# CONNECTIONS.net
KiCad netlist of a schematic drawn in Altium Designer
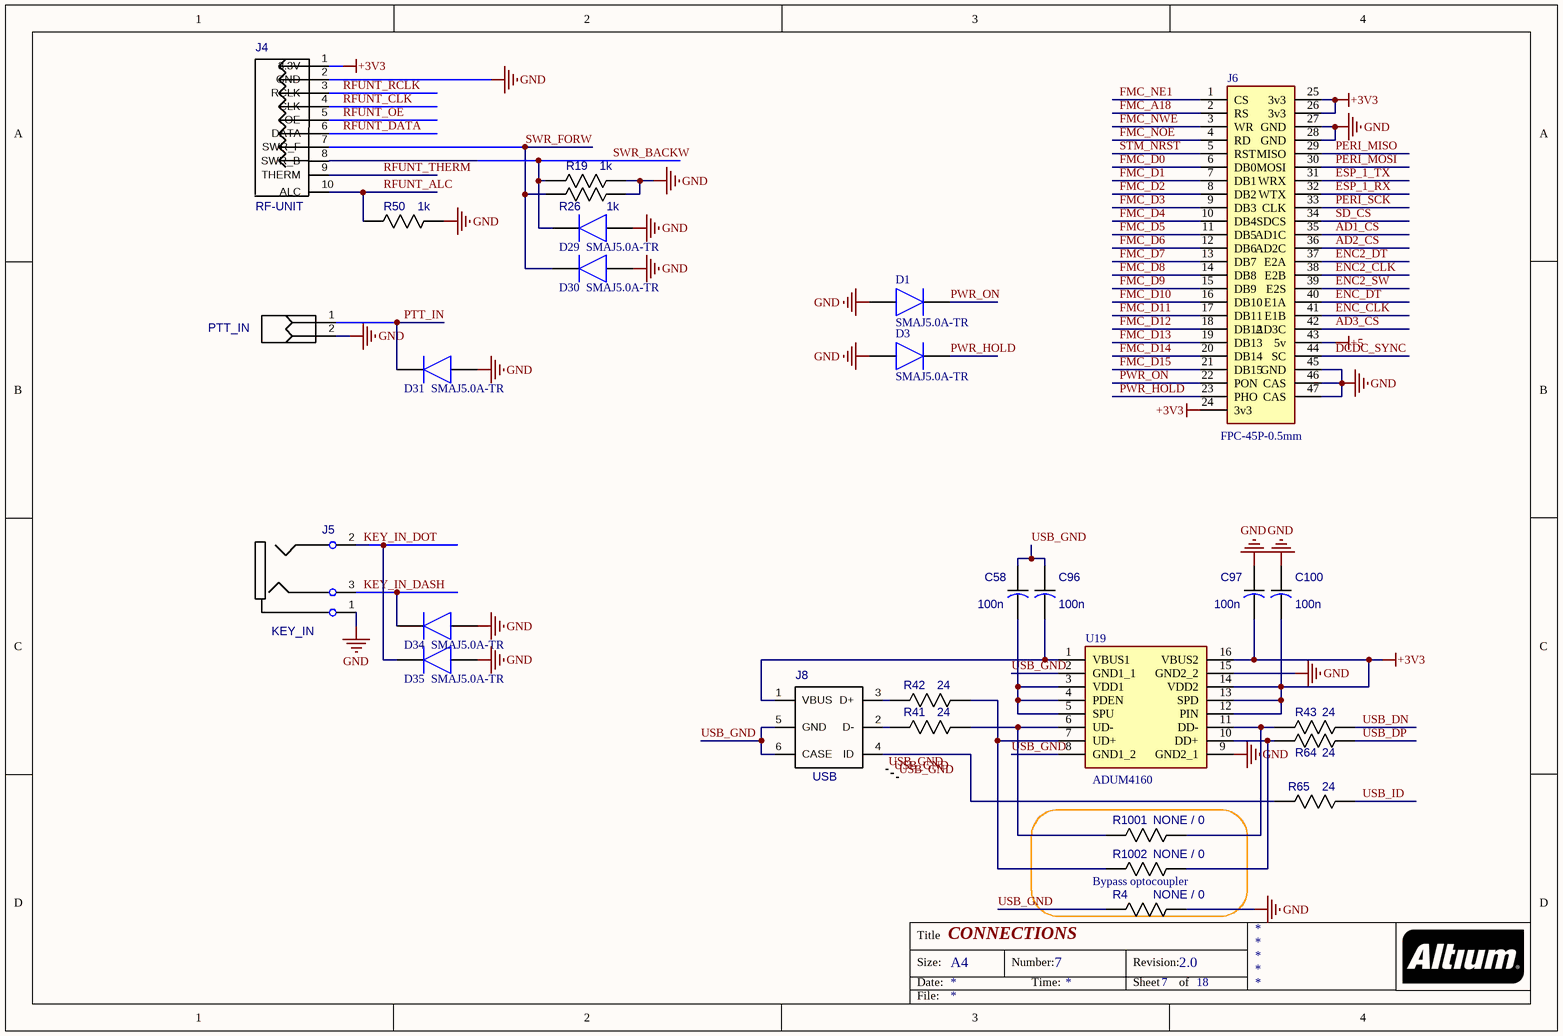
[diagram p0: CONNECTIONS.SchDoc]

(export (version "E")
  (design (tool "Eeschema 10.0.6"))
  (components
    (comp (ref "C58")
      (value "100n")
      (footprint "CAP_0805")
      (description "CAP_0805")
      (libsource (lib "*") (part "CAP_0805"))
    )
    (comp (ref "C96")
      (value "100n")
      (footprint "CAP_0805")
      (description "CAP_0805")
      (libsource (lib "*") (part "CAP_0805"))
    )
    (comp (ref "C97")
      (value "100n")
      (footprint "CAP_0805")
      (description "CAP_0805")
      (libsource (lib "*") (part "CAP_0805"))
    )
    (comp (ref "C100")
      (value "100n")
      (footprint "CAP_0805")
      (description "CAP_0805")
      (libsource (lib "*") (part "CAP_0805"))
    )
    (comp (ref "D1")
      (value "SMAJ5.0A-TR")
      (footprint "SMBJ36CATR")
      (description "Diode")
      (fields
        (field (name "MANUFACTURER_PART_NUMBER") "SMLVT3V3")
        (field (name "MOUSER PART NUMBER") "511-SMLVT3V3")
      )
      (libsource (lib "*") (part "SMLVT3V3"))
    )
    (comp (ref "D3")
      (value "SMAJ5.0A-TR")
      (footprint "SMBJ36CATR")
      (description "Diode")
      (fields
        (field (name "MANUFACTURER_PART_NUMBER") "SMLVT3V3")
        (field (name "MOUSER PART NUMBER") "511-SMLVT3V3")
      )
      (libsource (lib "*") (part "SMLVT3V3"))
    )
    (comp (ref "D29")
      (value "SMAJ5.0A-TR")
      (footprint "SamacSys:SMBJ36CATR")
      (description "Diode")
      (fields
        (field (name "MANUFACTURER_PART_NUMBER") "SMLVT3V3")
        (field (name "MOUSER PART NUMBER") "511-SMLVT3V3")
      )
      (libsource (lib "*") (part "SMLVT3V3"))
    )
    (comp (ref "D30")
      (value "SMAJ5.0A-TR")
      (footprint "SMBJ36CATR")
      (description "Diode")
      (fields
        (field (name "MANUFACTURER_PART_NUMBER") "SMLVT3V3")
        (field (name "MOUSER PART NUMBER") "511-SMLVT3V3")
      )
      (libsource (lib "*") (part "SMLVT3V3"))
    )
    (comp (ref "D31")
      (value "SMAJ5.0A-TR")
      (footprint "SamacSys:SMBJ36CATR")
      (description "Diode")
      (fields
        (field (name "MANUFACTURER_PART_NUMBER") "SMLVT3V3")
        (field (name "MOUSER PART NUMBER") "511-SMLVT3V3")
      )
      (libsource (lib "*") (part "SMLVT3V3"))
    )
    (comp (ref "D34")
      (value "SMAJ5.0A-TR")
      (footprint "SamacSys:SMBJ36CATR")
      (description "Diode")
      (fields
        (field (name "MANUFACTURER_PART_NUMBER") "SMLVT3V3")
        (field (name "MOUSER PART NUMBER") "511-SMLVT3V3")
      )
      (libsource (lib "*") (part "SMLVT3V3"))
    )
    (comp (ref "D35")
      (value "SMAJ5.0A-TR")
      (footprint "SamacSys:SMBJ36CATR")
      (description "Diode")
      (fields
        (field (name "MANUFACTURER_PART_NUMBER") "SMLVT3V3")
        (field (name "MOUSER PART NUMBER") "511-SMLVT3V3")
      )
      (libsource (lib "*") (part "SMLVT3V3"))
    )
    (comp (ref "J4")
      (value "RF-UNIT")
      (footprint "90131-0126")
      (description "2*5 Pin")
      (libsource (lib "MOTHERBOARD") (part "90131-0126"))
    )
    (comp (ref "J5")
      (value "KEY_IN")
      (footprint "SJ1-3525NG")
      (description "SJ1-3525NG")
      (libsource (lib "*") (part "SJ1-3523N"))
    )
    (comp (ref "J6")
      (value "FPC-45P-0.5mm")
      (footprint "MOTHERBOARD:FH12S45S05SH60")
      (description "Connector")
      (fields
        (field (name "MANUFACTURER_PART_NUMBER") "FH12S-45S-0.5SH(55)")
        (field (name "MOUSER PART NUMBER") "798-FH12S-45S-05SH55")
      )
      (libsource (lib "*") (part "FH12S-45S-0.5SH_55_"))
    )
    (comp (ref "J8")
      (value "USB")
      (footprint "2-1734035-3")
      (description "2-1734035-3")
      (libsource (lib "*") (part "2-1734035-3"))
    )
    (comp (ref "PTT_IN")
      (value "PTT_IN")
      (footprint "51022-0200")
      (description "51022-0200")
      (libsource (lib "*") (part "51022-0200"))
    )
    (comp (ref "R4")
      (value "NONE / 0")
      (footprint "RES_0805")
      (description "RES_0805")
      (libsource (lib "*") (part "RES_0805"))
    )
    (comp (ref "R19")
      (value "1k")
      (footprint "RES_0805")
      (description "RES_0805")
      (libsource (lib "*") (part "RES_0805"))
    )
    (comp (ref "R26")
      (value "1k")
      (footprint "RES_0805")
      (description "RES_0805")
      (libsource (lib "*") (part "RES_0805"))
    )
    (comp (ref "R41")
      (value "24")
      (footprint "RES_0805")
      (description "RES_0805")
      (libsource (lib "*") (part "RES_0805"))
    )
    (comp (ref "R42")
      (value "24")
      (footprint "RES_0805")
      (description "RES_0805")
      (libsource (lib "*") (part "RES_0805"))
    )
    (comp (ref "R43")
      (value "24")
      (footprint "RES_0805")
      (description "RES_0805")
      (libsource (lib "*") (part "RES_0805"))
    )
    (comp (ref "R50")
      (value "1k")
      (footprint "RES_0805")
      (description "RES_0805")
      (libsource (lib "*") (part "RES_0805"))
    )
    (comp (ref "R64")
      (value "24")
      (footprint "RES_0805")
      (description "RES_0805")
      (libsource (lib "*") (part "RES_0805"))
    )
    (comp (ref "R65")
      (value "24")
      (footprint "RES_0805")
      (description "RES_0805")
      (libsource (lib "*") (part "RES_0805"))
    )
    (comp (ref "R1001")
      (value "NONE / 0")
      (footprint "RES_0805")
      (description "RES_0805")
      (libsource (lib "*") (part "RES_0805"))
    )
    (comp (ref "R1002")
      (value "NONE / 0")
      (footprint "RES_0805")
      (description "RES_0805")
      (libsource (lib "*") (part "RES_0805"))
    )
    (comp (ref "U19")
      (value "ADUM4160")
      (footprint "SOIC127P1032X265-16N")
      (description "Integrated Circuit")
      (fields
        (field (name "MANUFACTURER_PART_NUMBER") "ADUM4160BRWZ")
        (field (name "MOUSER PART NUMBER") "584-ADUM4160BRWZ")
      )
      (libsource (lib "*") (part "ADUM4160BRWZ"))
    )
  )
  (nets
    (net (code "1") (name "+3V3") (class "Default")
      (node (ref "C100") (pin "2") (pinfunction "2_2") (pintype "passive"))
      (node (ref "C97") (pin "2") (pinfunction "2_2") (pintype "passive"))
      (node (ref "J4") (pin "1") (pinfunction "3.3V_1") (pintype "passive"))
      (node (ref "J6") (pin "24") (pinfunction "3v3_24") (pintype "passive"))
      (node (ref "J6") (pin "25") (pinfunction "3v3_25") (pintype "passive"))
      (node (ref "J6") (pin "26") (pinfunction "3v3_26") (pintype "passive"))
      (node (ref "U19") (pin "12") (pinfunction "PIN_12") (pintype "passive"))
      (node (ref "U19") (pin "13") (pinfunction "SPD_13") (pintype "passive"))
      (node (ref "U19") (pin "14") (pinfunction "VDD2_14") (pintype "passive"))
      (node (ref "U19") (pin "16") (pinfunction "VBUS2_16") (pintype "passive"))
    )
    (net (code "2") (name "+5") (class "Default")
      (node (ref "J6") (pin "43") (pinfunction "5v_43") (pintype "passive"))
    )
    (net (code "3") (name "/AD1_CS") (class "Default")
      (node (ref "J6") (pin "35") (pinfunction "AD1C_35") (pintype "passive"))
    )
    (net (code "4") (name "/AD2_CS") (class "Default")
      (node (ref "J6") (pin "36") (pinfunction "AD2C_36") (pintype "passive"))
    )
    (net (code "5") (name "/AD3_CS") (class "Default")
      (node (ref "J6") (pin "42") (pinfunction "AD3C_42") (pintype "passive"))
    )
    (net (code "6") (name "/DCDC_SYNC") (class "Default")
      (node (ref "J6") (pin "44") (pinfunction "SC_44") (pintype "passive"))
    )
    (net (code "7") (name "/ENC2_CLK") (class "Default")
      (node (ref "J6") (pin "38") (pinfunction "E2B_38") (pintype "passive"))
    )
    (net (code "8") (name "/ENC2_DT") (class "Default")
      (node (ref "J6") (pin "37") (pinfunction "E2A_37") (pintype "passive"))
    )
    (net (code "9") (name "/ENC2_SW") (class "Default")
      (node (ref "J6") (pin "39") (pinfunction "E2S_39") (pintype "passive"))
    )
    (net (code "10") (name "/ENC_CLK") (class "Default")
      (node (ref "J6") (pin "41") (pinfunction "E1B_41") (pintype "passive"))
    )
    (net (code "11") (name "/ENC_DT") (class "Default")
      (node (ref "J6") (pin "40") (pinfunction "E1A_40") (pintype "passive"))
    )
    (net (code "12") (name "/ESP_1_RX") (class "Default")
      (node (ref "J6") (pin "32") (pinfunction "WTX_32") (pintype "passive"))
    )
    (net (code "13") (name "/ESP_1_TX") (class "Default")
      (node (ref "J6") (pin "31") (pinfunction "WRX_31") (pintype "passive"))
    )
    (net (code "14") (name "/FMC_A18") (class "Default")
      (node (ref "J6") (pin "2") (pinfunction "RS_2") (pintype "passive"))
    )
    (net (code "15") (name "/FMC_D0") (class "Default")
      (node (ref "J6") (pin "6") (pinfunction "DB0_6") (pintype "passive"))
    )
    (net (code "16") (name "/FMC_D1") (class "Default")
      (node (ref "J6") (pin "7") (pinfunction "DB1_7") (pintype "passive"))
    )
    (net (code "17") (name "/FMC_D2") (class "Default")
      (node (ref "J6") (pin "8") (pinfunction "DB2_8") (pintype "passive"))
    )
    (net (code "18") (name "/FMC_D3") (class "Default")
      (node (ref "J6") (pin "9") (pinfunction "DB3_9") (pintype "passive"))
    )
    (net (code "19") (name "/FMC_D4") (class "Default")
      (node (ref "J6") (pin "10") (pinfunction "DB4_10") (pintype "passive"))
    )
    (net (code "20") (name "/FMC_D5") (class "Default")
      (node (ref "J6") (pin "11") (pinfunction "DB5_11") (pintype "passive"))
    )
    (net (code "21") (name "/FMC_D6") (class "Default")
      (node (ref "J6") (pin "12") (pinfunction "DB6_12") (pintype "passive"))
    )
    (net (code "22") (name "/FMC_D7") (class "Default")
      (node (ref "J6") (pin "13") (pinfunction "DB7_13") (pintype "passive"))
    )
    (net (code "23") (name "/FMC_D8") (class "Default")
      (node (ref "J6") (pin "14") (pinfunction "DB8_14") (pintype "passive"))
    )
    (net (code "24") (name "/FMC_D9") (class "Default")
      (node (ref "J6") (pin "15") (pinfunction "DB9_15") (pintype "passive"))
    )
    (net (code "25") (name "/FMC_D10") (class "Default")
      (node (ref "J6") (pin "16") (pinfunction "DB10_16") (pintype "passive"))
    )
    (net (code "26") (name "/FMC_D11") (class "Default")
      (node (ref "J6") (pin "17") (pinfunction "DB11_17") (pintype "passive"))
    )
    (net (code "27") (name "/FMC_D12") (class "Default")
      (node (ref "J6") (pin "18") (pinfunction "DB12_18") (pintype "passive"))
    )
    (net (code "28") (name "/FMC_D13") (class "Default")
      (node (ref "J6") (pin "19") (pinfunction "DB13_19") (pintype "passive"))
    )
    (net (code "29") (name "/FMC_D14") (class "Default")
      (node (ref "J6") (pin "20") (pinfunction "DB14_20") (pintype "passive"))
    )
    (net (code "30") (name "/FMC_D15") (class "Default")
      (node (ref "J6") (pin "21") (pinfunction "DB15_21") (pintype "passive"))
    )
    (net (code "31") (name "/FMC_NE1") (class "Default")
      (node (ref "J6") (pin "1") (pinfunction "CS_1") (pintype "passive"))
    )
    (net (code "32") (name "/FMC_NOE") (class "Default")
      (node (ref "J6") (pin "4") (pinfunction "RD_4") (pintype "passive"))
    )
    (net (code "33") (name "/FMC_NWE") (class "Default")
      (node (ref "J6") (pin "3") (pinfunction "WR_3") (pintype "passive"))
    )
    (net (code "34") (name "/KEY_IN_DASH") (class "Default")
      (node (ref "D34") (pin "1") (pinfunction "K_1") (pintype "passive"))
      (node (ref "J5") (pin "3") (pinfunction "ring_3") (pintype "passive"))
    )
    (net (code "35") (name "/KEY_IN_DOT") (class "Default")
      (node (ref "D35") (pin "1") (pinfunction "K_1") (pintype "passive"))
      (node (ref "J5") (pin "2") (pinfunction "tip_2") (pintype "passive"))
    )
    (net (code "36") (name "/PERI_MISO") (class "Default")
      (node (ref "J6") (pin "29") (pinfunction "MISO_29") (pintype "passive"))
    )
    (net (code "37") (name "/PERI_MOSI") (class "Default")
      (node (ref "J6") (pin "30") (pinfunction "MOSI_30") (pintype "passive"))
    )
    (net (code "38") (name "/PERI_SCK") (class "Default")
      (node (ref "J6") (pin "33") (pinfunction "CLK_33") (pintype "passive"))
    )
    (net (code "39") (name "/PTT_IN") (class "Default")
      (node (ref "D31") (pin "1") (pinfunction "K_1") (pintype "passive"))
      (node (ref "PTT_IN") (pin "1") (pinfunction "1_1") (pintype "passive"))
    )
    (net (code "40") (name "/PWR_HOLD") (class "Default")
      (node (ref "D3") (pin "1") (pinfunction "K_1") (pintype "passive"))
      (node (ref "J6") (pin "23") (pinfunction "PHO_23") (pintype "passive"))
    )
    (net (code "41") (name "/PWR_ON") (class "Default")
      (node (ref "D1") (pin "1") (pinfunction "K_1") (pintype "passive"))
      (node (ref "J6") (pin "22") (pinfunction "PON_22") (pintype "passive"))
    )
    (net (code "42") (name "/RFUNT_ALC") (class "Default")
      (node (ref "J4") (pin "10") (pinfunction "ALC_10") (pintype "passive"))
      (node (ref "R50") (pin "1") (pinfunction "1_1") (pintype "passive"))
    )
    (net (code "43") (name "/RFUNT_CLK") (class "Default")
      (node (ref "J4") (pin "4") (pinfunction "CLK_4") (pintype "passive"))
    )
    (net (code "44") (name "/RFUNT_DATA") (class "Default")
      (node (ref "J4") (pin "6") (pinfunction "DATA_6") (pintype "passive"))
    )
    (net (code "45") (name "/RFUNT_OE") (class "Default")
      (node (ref "J4") (pin "5") (pinfunction "OE_5") (pintype "passive"))
    )
    (net (code "46") (name "/RFUNT_RCLK") (class "Default")
      (node (ref "J4") (pin "3") (pinfunction "RCLK_3") (pintype "passive"))
    )
    (net (code "47") (name "/RFUNT_THERM") (class "Default")
      (node (ref "J4") (pin "9") (pinfunction "THERM_9") (pintype "passive"))
    )
    (net (code "48") (name "/SD_CS") (class "Default")
      (node (ref "J6") (pin "34") (pinfunction "SDCS_34") (pintype "passive"))
    )
    (net (code "49") (name "/STM_NRST") (class "Default")
      (node (ref "J6") (pin "5") (pinfunction "RST_5") (pintype "passive"))
    )
    (net (code "50") (name "/SWR_BACKW") (class "Default")
      (node (ref "D29") (pin "1") (pinfunction "K_1") (pintype "passive"))
      (node (ref "J4") (pin "8") (pinfunction "SWR_B_8") (pintype "passive"))
      (node (ref "R19") (pin "1") (pinfunction "1_1") (pintype "passive"))
    )
    (net (code "51") (name "/SWR_FORW") (class "Default")
      (node (ref "D30") (pin "1") (pinfunction "K_1") (pintype "passive"))
      (node (ref "J4") (pin "7") (pinfunction "SWR_F_7") (pintype "passive"))
      (node (ref "R26") (pin "1") (pinfunction "1_1") (pintype "passive"))
    )
    (net (code "52") (name "/USB_DN") (class "Default")
      (node (ref "R43") (pin "2") (pinfunction "2_2") (pintype "passive"))
    )
    (net (code "53") (name "/USB_DP") (class "Default")
      (node (ref "R64") (pin "2") (pinfunction "2_2") (pintype "passive"))
    )
    (net (code "54") (name "/USB_GND") (class "Default")
      (node (ref "C58") (pin "1") (pinfunction "1_1") (pintype "passive"))
      (node (ref "C96") (pin "1") (pinfunction "1_1") (pintype "passive"))
      (node (ref "J8") (pin "5") (pinfunction "GND_5") (pintype "passive"))
      (node (ref "J8") (pin "6") (pinfunction "CASE_6") (pintype "passive"))
      (node (ref "J8") (pin "7") (pinfunction "0_7") (pintype "passive"))
      (node (ref "J8") (pin "8") (pinfunction "0_8") (pintype "passive"))
      (node (ref "J8") (pin "9") (pinfunction "0_9") (pintype "passive"))
      (node (ref "R4") (pin "1") (pinfunction "1_1") (pintype "passive"))
      (node (ref "U19") (pin "2") (pinfunction "GND1_1_2") (pintype "passive"))
      (node (ref "U19") (pin "8") (pinfunction "GND1_2_8") (pintype "passive"))
    )
    (net (code "55") (name "/USB_ID") (class "Default")
      (node (ref "R65") (pin "2") (pinfunction "2_2") (pintype "passive"))
    )
    (net (code "56") (name "GND") (class "Default")
      (node (ref "C100") (pin "1") (pinfunction "1_1") (pintype "passive"))
      (node (ref "C97") (pin "1") (pinfunction "1_1") (pintype "passive"))
      (node (ref "D1") (pin "2") (pinfunction "A_2") (pintype "passive"))
      (node (ref "D29") (pin "2") (pinfunction "A_2") (pintype "passive"))
      (node (ref "D3") (pin "2") (pinfunction "A_2") (pintype "passive"))
      (node (ref "D30") (pin "2") (pinfunction "A_2") (pintype "passive"))
      (node (ref "D31") (pin "2") (pinfunction "A_2") (pintype "passive"))
      (node (ref "D34") (pin "2") (pinfunction "A_2") (pintype "passive"))
      (node (ref "D35") (pin "2") (pinfunction "A_2") (pintype "passive"))
      (node (ref "J4") (pin "2") (pinfunction "GND_2") (pintype "passive"))
      (node (ref "J5") (pin "1") (pinfunction "sleeve_1") (pintype "passive"))
      (node (ref "J6") (pin "27") (pinfunction "GND_27") (pintype "passive"))
      (node (ref "J6") (pin "28") (pinfunction "GND_28") (pintype "passive"))
      (node (ref "J6") (pin "45") (pinfunction "GND_45") (pintype "passive"))
      (node (ref "J6") (pin "46") (pinfunction "CAS_46") (pintype "passive"))
      (node (ref "J6") (pin "47") (pinfunction "CAS_47") (pintype "passive"))
      (node (ref "PTT_IN") (pin "2") (pinfunction "2_2") (pintype "passive"))
      (node (ref "R19") (pin "2") (pinfunction "2_2") (pintype "passive"))
      (node (ref "R26") (pin "2") (pinfunction "2_2") (pintype "passive"))
      (node (ref "R4") (pin "2") (pinfunction "2_2") (pintype "passive"))
      (node (ref "R50") (pin "2") (pinfunction "2_2") (pintype "passive"))
      (node (ref "U19") (pin "15") (pinfunction "GND2_2_15") (pintype "passive"))
      (node (ref "U19") (pin "9") (pinfunction "GND2_1_9") (pintype "passive"))
    )
    (net (code "57") (name "Net-(J8-D+)") (class "Default")
      (node (ref "J8") (pin "3") (pinfunction "D+_3") (pintype "passive"))
      (node (ref "R42") (pin "1") (pinfunction "1_1") (pintype "passive"))
    )
    (net (code "58") (name "Net-(J8-D-)") (class "Default")
      (node (ref "J8") (pin "2") (pinfunction "D-_2") (pintype "passive"))
      (node (ref "R41") (pin "1") (pinfunction "1_1") (pintype "passive"))
    )
    (net (code "59") (name "Net-(J8-ID)") (class "Default")
      (node (ref "J8") (pin "4") (pinfunction "ID_4") (pintype "passive"))
      (node (ref "R65") (pin "1") (pinfunction "1_1") (pintype "passive"))
    )
    (net (code "60") (name "Net-(J8-VBUS)") (class "Default")
      (node (ref "C96") (pin "2") (pinfunction "2_2") (pintype "passive"))
      (node (ref "J8") (pin "1") (pinfunction "VBUS_1") (pintype "passive"))
      (node (ref "U19") (pin "1") (pinfunction "VBUS1_1") (pintype "passive"))
    )
    (net (code "61") (name "Net-(U19-DD+)") (class "Default")
      (node (ref "R1002") (pin "2") (pinfunction "2_2") (pintype "passive"))
      (node (ref "R64") (pin "1") (pinfunction "1_1") (pintype "passive"))
      (node (ref "U19") (pin "10") (pinfunction "DD+_10") (pintype "passive"))
    )
    (net (code "62") (name "Net-(U19-DD-)") (class "Default")
      (node (ref "R1001") (pin "2") (pinfunction "2_2") (pintype "passive"))
      (node (ref "R43") (pin "1") (pinfunction "1_1") (pintype "passive"))
      (node (ref "U19") (pin "11") (pinfunction "DD-_11") (pintype "passive"))
    )
    (net (code "63") (name "Net-(U19-PDEN)") (class "Default")
      (node (ref "C58") (pin "2") (pinfunction "2_2") (pintype "passive"))
      (node (ref "U19") (pin "3") (pinfunction "VDD1_3") (pintype "passive"))
      (node (ref "U19") (pin "4") (pinfunction "PDEN_4") (pintype "passive"))
      (node (ref "U19") (pin "5") (pinfunction "SPU_5") (pintype "passive"))
    )
    (net (code "64") (name "Net-(U19-UD+)") (class "Default")
      (node (ref "R1002") (pin "1") (pinfunction "1_1") (pintype "passive"))
      (node (ref "R42") (pin "2") (pinfunction "2_2") (pintype "passive"))
      (node (ref "U19") (pin "7") (pinfunction "UD+_7") (pintype "passive"))
    )
    (net (code "65") (name "Net-(U19-UD-)") (class "Default")
      (node (ref "R1001") (pin "1") (pinfunction "1_1") (pintype "passive"))
      (node (ref "R41") (pin "2") (pinfunction "2_2") (pintype "passive"))
      (node (ref "U19") (pin "6") (pinfunction "UD-_6") (pintype "passive"))
    )
  )
)
